# MODULE_PINOUT_WIFI_LAMP_CONTROL.net
KiCad netlist of a schematic drawn in Altium Designer
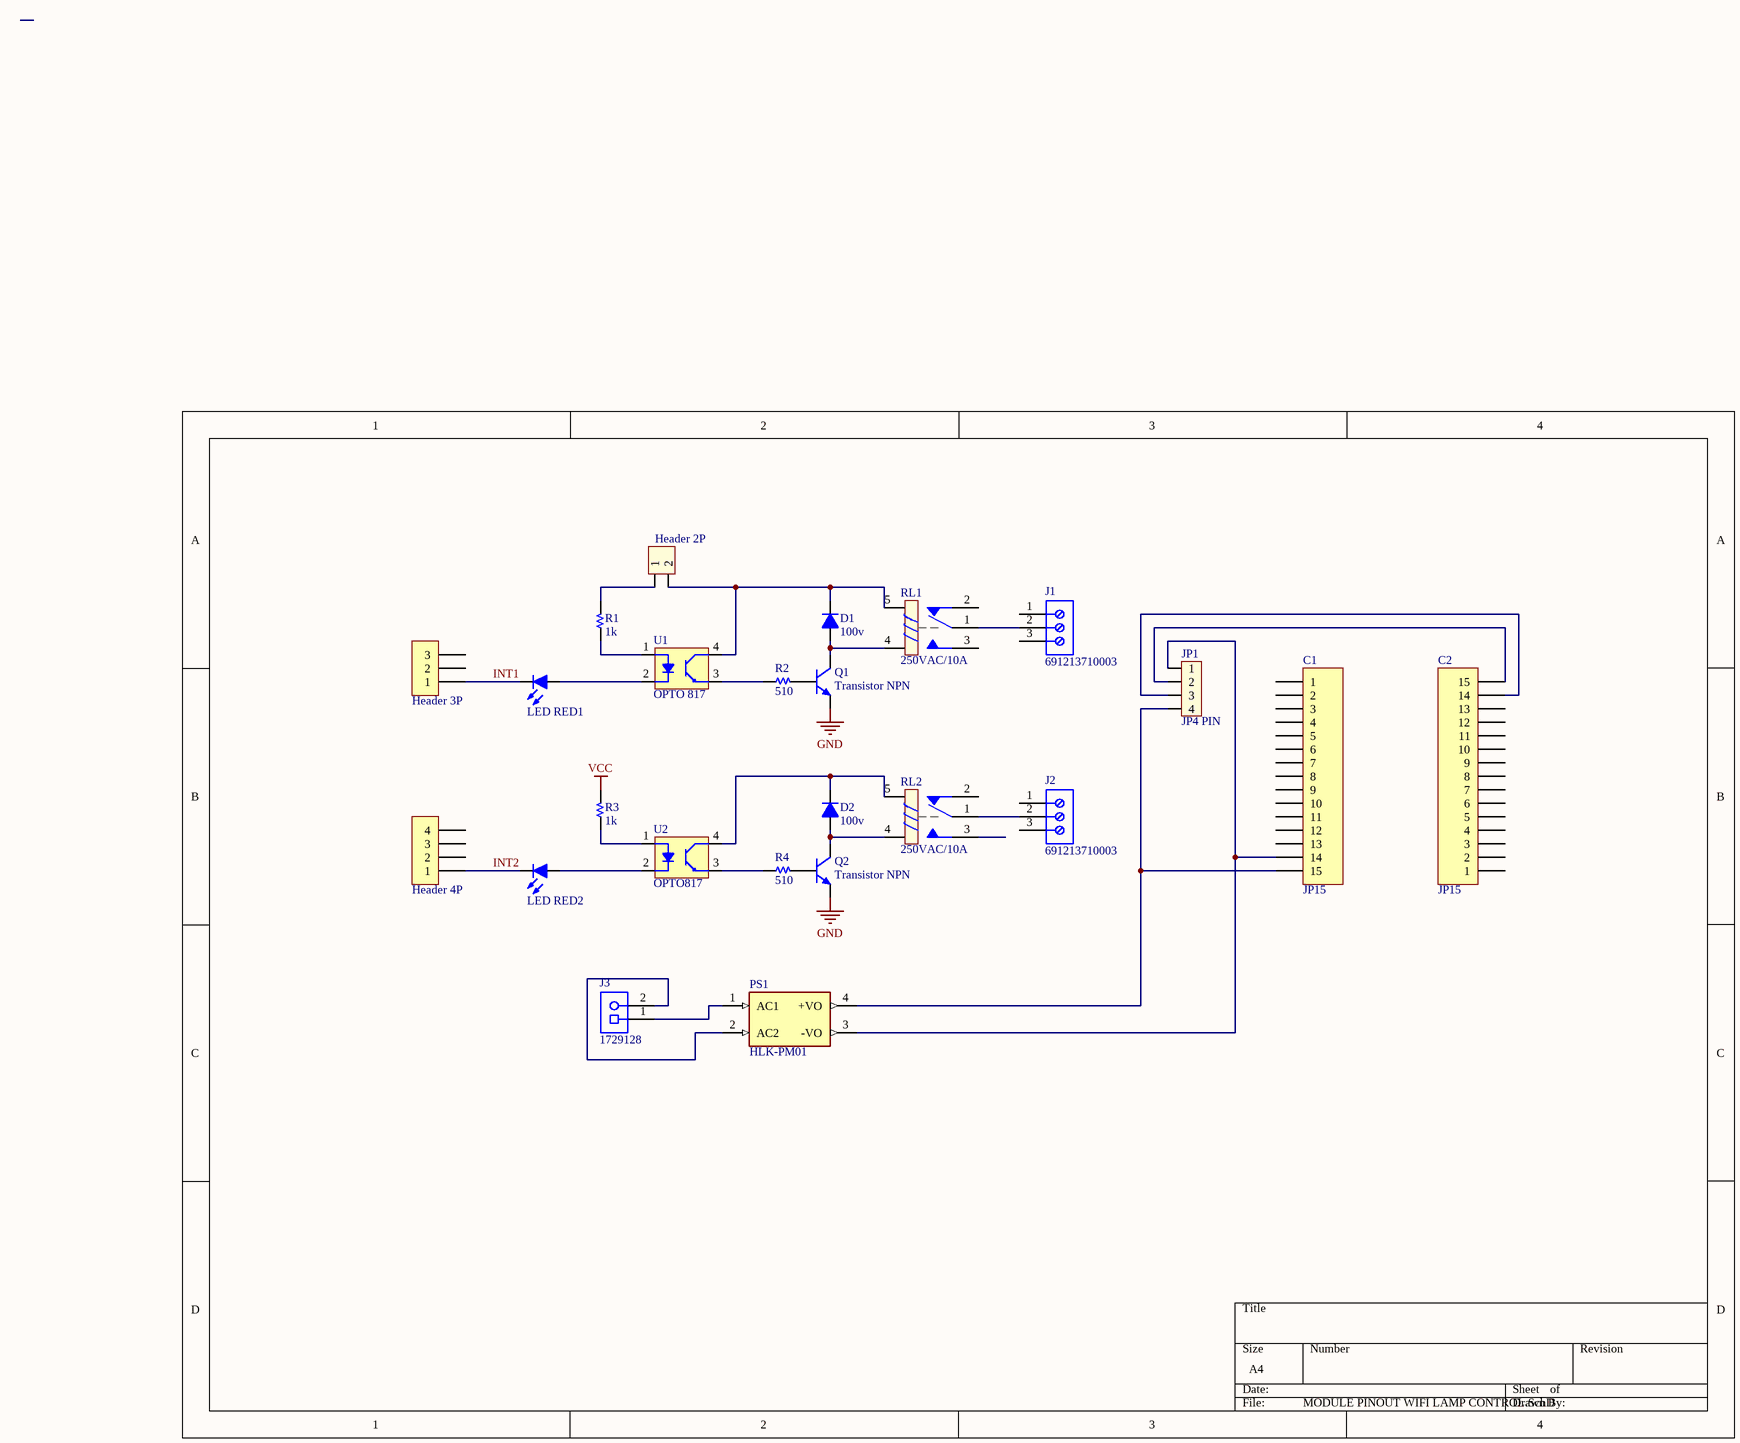
[diagram p0: MODULE PINOUT WIFI LAMP CONTROL.SchDoc]

(export (version "E")
  (design (tool "Eeschema 10.0.6"))
  (components
    (comp (ref "C1")
      (value "JP15")
      (footprint "JP15-C1T")
      (description "WR-PHD 2.54 mm Angled Socket Header")
      (fields
        (field (name "MANUFACTURER") "Würth Elektronik eiSos GmbH")
        (field (name "PARTNO") "613015143121")
        (field (name "CREATED BY") "Karrer Zheng")
      )
      (libsource (lib "") (part "JP15_1"))
    )
    (comp (ref "C2")
      (value "JP15")
      (footprint "JP15-C1T")
      (description "WR-PHD 2.54 mm Angled Socket Header")
      (fields
        (field (name "MANUFACTURER") "Würth Elektronik eiSos GmbH")
        (field (name "PARTNO") "613015143121")
        (field (name "CREATED BY") "Karrer Zheng")
      )
      (libsource (lib "LIBRARY") (part "JP15"))
    )
    (comp (ref "D1")
      (value "100v")
      (footprint "DIODE 0.5A")
      (description "Cắm")
      (libsource (lib "Altium_Lib_by_KhueNguyenCreator") (part "Diode 1N4148"))
    )
    (comp (ref "D2")
      (value "100v")
      (footprint "DIODE 0.5A")
      (description "Cắm")
      (libsource (lib "Altium_Lib_by_KhueNguyenCreator") (part "Diode 1N4148"))
    )
    (comp (ref "H1")
      (value "Header 2P")
      (footprint "XH2.54M-2")
      (description "Cắm")
      (libsource (lib "Altium_Lib_by_KhueNguyenCreator") (part "Header 2P 2.54 Duc Thang"))
    )
    (comp (ref "H2")
      (value "Header 3P")
      (footprint "XH2.54M-3")
      (description "Cắm")
      (libsource (lib "Altium_Lib_by_KhueNguyenCreator") (part "Header 3P 2.54 Duc Thang"))
    )
    (comp (ref "H3")
      (value "Header 4P")
      (footprint "XH2.54M-4")
      (description "Cắm")
      (libsource (lib "Altium_Lib_by_KhueNguyenCreator") (part "Header 4P 2.54 Duc Thang"))
    )
    (comp (ref "J1")
      (value "691213710003")
      (footprint "691213710003")
      (fields (field (name "VOLTAGE") "300V"))
      (libsource (lib "Terminal Block") (part "CMP-1502-02527-2"))
    )
    (comp (ref "J2")
      (value "691213710003")
      (footprint "691213710003")
      (fields (field (name "VOLTAGE") "300V"))
      (libsource (lib "Terminal Block") (part "CMP-1502-02527-2"))
    )
    (comp (ref "J3")
      (value "1729128")
      (footprint "PHOE-1729128-2_V")
      (description "PCB Terminal Block, 13.5 A, 400 V, 2-Pin THD, RoHS, Bulk")
      (fields (field (name "MANUFACTURER") "Phoenix Contact"))
      (libsource (lib "2P Screw Terminal Block") (part "CMP-2000-05815-1"))
    )
    (comp (ref "JP1") (value "JP4 PIN") (footprint "JP4") (libsource (lib "Cty1") (part "JP4")))
    (comp (ref "LED RED1")
      (value "LED RED")
      (footprint "LED 5MM - RED")
      (description "Typical LED")
      (libsource (lib "chipfc_altium_libs") (part "Led"))
    )
    (comp (ref "LED RED2")
      (value "LED RED")
      (footprint "LED 5MM - RED")
      (description "Typical LED")
      (libsource (lib "chipfc_altium_libs") (part "Led"))
    )
    (comp (ref "PS1")
      (value "HLK-PM01")
      (footprint "CONV_HLK-PM01")
      (fields (field (name "MF") "Hi-link") (field (name "MP") "hlk-pm01"))
      (libsource (lib "HLK-PM01") (part "HLK-PM01"))
    )
    (comp (ref "Q1")
      (value "Transistor NPN")
      (footprint "SOT-23")
      (description "NPN Bipolar Transistor")
      (libsource (lib "chipfc_altium_libs") (part "Transistor NPN"))
    )
    (comp (ref "Q2")
      (value "Transistor NPN")
      (footprint "SOT-23")
      (description "NPN Bipolar Transistor")
      (libsource (lib "chipfc_altium_libs") (part "Transistor NPN"))
    )
    (comp (ref "R1")
      (value "1k")
      (footprint "R 1/4W/300")
      (description "Resistor")
      (libsource (lib "chipfc_altium_libs") (part "Resistor"))
    )
    (comp (ref "R2")
      (value "510")
      (footprint "R 1/4W/300")
      (description "Resistor")
      (libsource (lib "chipfc_altium_libs") (part "Resistor"))
    )
    (comp (ref "R3")
      (value "1k")
      (footprint "R 1/4W/300")
      (description "Resistor")
      (libsource (lib "chipfc_altium_libs") (part "Resistor"))
    )
    (comp (ref "R4")
      (value "510")
      (footprint "R 1/4W/300")
      (description "Resistor")
      (libsource (lib "chipfc_altium_libs") (part "Resistor"))
    )
    (comp (ref "RL1")
      (value "250VAC/10A")
      (footprint "Relay 5 Chan SRD")
      (description "Relay 5 Chan")
      (libsource (lib "Altium_Lib_by_KhueNguyenCreator") (part "Relay 5 Chan SRD"))
    )
    (comp (ref "RL2")
      (value "250VAC/10A")
      (footprint "Relay 5 Chan SRD")
      (description "Relay 5 Chan")
      (libsource (lib "Altium_Lib_by_KhueNguyenCreator") (part "Relay 5 Chan SRD"))
    )
    (comp (ref "U1")
      (value "OPTO 817")
      (footprint "DIP4 - PC817")
      (description "Opto PC817B")
      (libsource (lib "chipfc_altium_libs") (part "PC817"))
    )
    (comp (ref "U2")
      (value "OPTO817")
      (footprint "DIP4 - PC817")
      (description "Opto PC817B")
      (libsource (lib "chipfc_altium_libs") (part "PC817"))
    )
  )
  (nets
    (net (code "1") (name "/INT1") (class "Default")
      (node (ref "H2") (pin "1") (pinfunction "1_1") (pintype "passive"))
      (node (ref "LED RED1") (pin "2") (pinfunction "K_2") (pintype "passive"))
    )
    (net (code "2") (name "/INT2") (class "Default")
      (node (ref "H3") (pin "1") (pinfunction "1_1") (pintype "passive"))
      (node (ref "LED RED2") (pin "2") (pinfunction "K_2") (pintype "passive"))
    )
    (net (code "3") (name "GND") (class "Default")
      (node (ref "Q1") (pin "2") (pinfunction "E_2") (pintype "passive"))
      (node (ref "Q2") (pin "2") (pinfunction "E_2") (pintype "passive"))
    )
    (net (code "4") (name "Net-(C2-Pad14)") (class "Default")
      (node (ref "C2") (pin "14") (pinfunction "14_14") (pintype "passive"))
      (node (ref "JP1") (pin "3") (pinfunction "3_3") (pintype "passive"))
    )
    (net (code "5") (name "Net-(C2-Pad15)") (class "Default")
      (node (ref "C2") (pin "15") (pinfunction "15_15") (pintype "passive"))
      (node (ref "JP1") (pin "2") (pinfunction "2_2") (pintype "passive"))
    )
    (net (code "6") (name "Net-(D1-A)") (class "Default")
      (node (ref "D1") (pin "1") (pinfunction "A_1") (pintype "passive"))
      (node (ref "Q1") (pin "3") (pinfunction "C_3") (pintype "passive"))
      (node (ref "RL1") (pin "4") (pinfunction "4_4") (pintype "passive"))
    )
    (net (code "7") (name "Net-(D1-K)") (class "Default")
      (node (ref "D1") (pin "2") (pinfunction "K_2") (pintype "passive"))
      (node (ref "H1") (pin "2") (pinfunction "2_2") (pintype "passive"))
      (node (ref "RL1") (pin "5") (pinfunction "5_5") (pintype "passive"))
      (node (ref "U1") (pin "4") (pinfunction "C_4") (pintype "passive"))
    )
    (net (code "8") (name "Net-(D2-A)") (class "Default")
      (node (ref "D2") (pin "1") (pinfunction "A_1") (pintype "passive"))
      (node (ref "Q2") (pin "3") (pinfunction "C_3") (pintype "passive"))
      (node (ref "RL2") (pin "4") (pinfunction "4_4") (pintype "passive"))
    )
    (net (code "9") (name "Net-(D2-K)") (class "Default")
      (node (ref "D2") (pin "2") (pinfunction "K_2") (pintype "passive"))
      (node (ref "RL2") (pin "5") (pinfunction "5_5") (pintype "passive"))
      (node (ref "U2") (pin "4") (pinfunction "C_4") (pintype "passive"))
    )
    (net (code "10") (name "Net-(H1-Pad1)") (class "Default")
      (node (ref "H1") (pin "1") (pinfunction "1_1") (pintype "passive"))
      (node (ref "R1") (pin "2") (pinfunction "2_2") (pintype "passive"))
    )
    (net (code "11") (name "Net-(J1-Pad2)") (class "Default")
      (node (ref "J1") (pin "2") (pinfunction "2_2") (pintype "passive"))
      (node (ref "RL1") (pin "1") (pinfunction "1_1") (pintype "passive"))
    )
    (net (code "12") (name "Net-(J2-Pad2)") (class "Default")
      (node (ref "J2") (pin "2") (pinfunction "2_2") (pintype "passive"))
      (node (ref "RL2") (pin "1") (pinfunction "1_1") (pintype "passive"))
    )
    (net (code "13") (name "Net-(LED RED1-A)") (class "Default")
      (node (ref "LED RED1") (pin "1") (pinfunction "A_1") (pintype "passive"))
      (node (ref "U1") (pin "2") (pinfunction "K_2") (pintype "passive"))
    )
    (net (code "14") (name "Net-(LED RED2-A)") (class "Default")
      (node (ref "LED RED2") (pin "1") (pinfunction "A_1") (pintype "passive"))
      (node (ref "U2") (pin "2") (pinfunction "K_2") (pintype "passive"))
    )
    (net (code "15") (name "Net-(PS1-+VO)") (class "Default")
      (node (ref "C1") (pin "15") (pinfunction "15_15") (pintype "passive"))
      (node (ref "JP1") (pin "4") (pinfunction "4_4") (pintype "passive"))
      (node (ref "PS1") (pin "4") (pinfunction "+VO_4") (pintype "output"))
    )
    (net (code "16") (name "Net-(PS1--VO)") (class "Default")
      (node (ref "C1") (pin "14") (pinfunction "14_14") (pintype "passive"))
      (node (ref "JP1") (pin "1") (pinfunction "1_1") (pintype "passive"))
      (node (ref "PS1") (pin "3") (pinfunction "-VO_3") (pintype "output"))
    )
    (net (code "17") (name "Net-(PS1-AC1)") (class "Default")
      (node (ref "J3") (pin "1") (pinfunction "1_1") (pintype "passive"))
      (node (ref "PS1") (pin "1") (pinfunction "AC1_1") (pintype "input"))
    )
    (net (code "18") (name "Net-(PS1-AC2)") (class "Default")
      (node (ref "J3") (pin "2") (pinfunction "2_2") (pintype "passive"))
      (node (ref "PS1") (pin "2") (pinfunction "AC2_2") (pintype "input"))
    )
    (net (code "19") (name "Net-(Q1-B)") (class "Default")
      (node (ref "Q1") (pin "1") (pinfunction "B_1") (pintype "passive"))
      (node (ref "R2") (pin "2") (pinfunction "2_2") (pintype "passive"))
    )
    (net (code "20") (name "Net-(Q2-B)") (class "Default")
      (node (ref "Q2") (pin "1") (pinfunction "B_1") (pintype "passive"))
      (node (ref "R4") (pin "2") (pinfunction "2_2") (pintype "passive"))
    )
    (net (code "21") (name "Net-(U1-A)") (class "Default")
      (node (ref "R1") (pin "1") (pinfunction "1_1") (pintype "passive"))
      (node (ref "U1") (pin "1") (pinfunction "A_1") (pintype "passive"))
    )
    (net (code "22") (name "Net-(U1-E)") (class "Default")
      (node (ref "R2") (pin "1") (pinfunction "1_1") (pintype "passive"))
      (node (ref "U1") (pin "3") (pinfunction "E_3") (pintype "passive"))
    )
    (net (code "23") (name "Net-(U2-A)") (class "Default")
      (node (ref "R3") (pin "1") (pinfunction "1_1") (pintype "passive"))
      (node (ref "U2") (pin "1") (pinfunction "A_1") (pintype "passive"))
    )
    (net (code "24") (name "Net-(U2-E)") (class "Default")
      (node (ref "R4") (pin "1") (pinfunction "1_1") (pintype "passive"))
      (node (ref "U2") (pin "3") (pinfunction "E_3") (pintype "passive"))
    )
    (net (code "25") (name "VCC") (class "Default")
      (node (ref "R3") (pin "2") (pinfunction "2_2") (pintype "passive"))
    )
    (net (code "26") (name "unconnected-(C1-Pad1)") (class "Default")
      (node (ref "C1") (pin "1") (pinfunction "1_1") (pintype "passive"))
    )
    (net (code "27") (name "unconnected-(C1-Pad2)") (class "Default")
      (node (ref "C1") (pin "2") (pinfunction "2_2") (pintype "passive"))
    )
    (net (code "28") (name "unconnected-(C1-Pad3)") (class "Default")
      (node (ref "C1") (pin "3") (pinfunction "3_3") (pintype "passive"))
    )
    (net (code "29") (name "unconnected-(C1-Pad4)") (class "Default")
      (node (ref "C1") (pin "4") (pinfunction "4_4") (pintype "passive"))
    )
    (net (code "30") (name "unconnected-(C1-Pad5)") (class "Default")
      (node (ref "C1") (pin "5") (pinfunction "5_5") (pintype "passive"))
    )
    (net (code "31") (name "unconnected-(C1-Pad6)") (class "Default")
      (node (ref "C1") (pin "6") (pinfunction "6_6") (pintype "passive"))
    )
    (net (code "32") (name "unconnected-(C1-Pad7)") (class "Default")
      (node (ref "C1") (pin "7") (pinfunction "7_7") (pintype "passive"))
    )
    (net (code "33") (name "unconnected-(C1-Pad8)") (class "Default")
      (node (ref "C1") (pin "8") (pinfunction "8_8") (pintype "passive"))
    )
    (net (code "34") (name "unconnected-(C1-Pad9)") (class "Default")
      (node (ref "C1") (pin "9") (pinfunction "9_9") (pintype "passive"))
    )
    (net (code "35") (name "unconnected-(C1-Pad10)") (class "Default")
      (node (ref "C1") (pin "10") (pinfunction "10_10") (pintype "passive"))
    )
    (net (code "36") (name "unconnected-(C1-Pad11)") (class "Default")
      (node (ref "C1") (pin "11") (pinfunction "11_11") (pintype "passive"))
    )
    (net (code "37") (name "unconnected-(C1-Pad12)") (class "Default")
      (node (ref "C1") (pin "12") (pinfunction "12_12") (pintype "passive"))
    )
    (net (code "38") (name "unconnected-(C1-Pad13)") (class "Default")
      (node (ref "C1") (pin "13") (pinfunction "13_13") (pintype "passive"))
    )
    (net (code "39") (name "unconnected-(C2-Pad1)") (class "Default")
      (node (ref "C2") (pin "1") (pinfunction "1_1") (pintype "passive"))
    )
    (net (code "40") (name "unconnected-(C2-Pad2)") (class "Default")
      (node (ref "C2") (pin "2") (pinfunction "2_2") (pintype "passive"))
    )
    (net (code "41") (name "unconnected-(C2-Pad3)") (class "Default")
      (node (ref "C2") (pin "3") (pinfunction "3_3") (pintype "passive"))
    )
    (net (code "42") (name "unconnected-(C2-Pad4)") (class "Default")
      (node (ref "C2") (pin "4") (pinfunction "4_4") (pintype "passive"))
    )
    (net (code "43") (name "unconnected-(C2-Pad5)") (class "Default")
      (node (ref "C2") (pin "5") (pinfunction "5_5") (pintype "passive"))
    )
    (net (code "44") (name "unconnected-(C2-Pad6)") (class "Default")
      (node (ref "C2") (pin "6") (pinfunction "6_6") (pintype "passive"))
    )
    (net (code "45") (name "unconnected-(C2-Pad7)") (class "Default")
      (node (ref "C2") (pin "7") (pinfunction "7_7") (pintype "passive"))
    )
    (net (code "46") (name "unconnected-(C2-Pad8)") (class "Default")
      (node (ref "C2") (pin "8") (pinfunction "8_8") (pintype "passive"))
    )
    (net (code "47") (name "unconnected-(C2-Pad9)") (class "Default")
      (node (ref "C2") (pin "9") (pinfunction "9_9") (pintype "passive"))
    )
    (net (code "48") (name "unconnected-(C2-Pad10)") (class "Default")
      (node (ref "C2") (pin "10") (pinfunction "10_10") (pintype "passive"))
    )
    (net (code "49") (name "unconnected-(C2-Pad11)") (class "Default")
      (node (ref "C2") (pin "11") (pinfunction "11_11") (pintype "passive"))
    )
    (net (code "50") (name "unconnected-(C2-Pad12)") (class "Default")
      (node (ref "C2") (pin "12") (pinfunction "12_12") (pintype "passive"))
    )
    (net (code "51") (name "unconnected-(C2-Pad13)") (class "Default")
      (node (ref "C2") (pin "13") (pinfunction "13_13") (pintype "passive"))
    )
    (net (code "52") (name "unconnected-(H2-Pad2)") (class "Default")
      (node (ref "H2") (pin "2") (pinfunction "2_2") (pintype "passive"))
    )
    (net (code "53") (name "unconnected-(H2-Pad3)") (class "Default")
      (node (ref "H2") (pin "3") (pinfunction "3_3") (pintype "passive"))
    )
    (net (code "54") (name "unconnected-(H3-Pad2)") (class "Default")
      (node (ref "H3") (pin "2") (pinfunction "2_2") (pintype "passive"))
    )
    (net (code "55") (name "unconnected-(H3-Pad3)") (class "Default")
      (node (ref "H3") (pin "3") (pinfunction "3_3") (pintype "passive"))
    )
    (net (code "56") (name "unconnected-(H3-Pad4)") (class "Default")
      (node (ref "H3") (pin "4") (pinfunction "4_4") (pintype "passive"))
    )
    (net (code "57") (name "unconnected-(J1-Pad1)") (class "Default")
      (node (ref "J1") (pin "1") (pinfunction "1_1") (pintype "passive"))
    )
    (net (code "58") (name "unconnected-(J1-Pad3)") (class "Default")
      (node (ref "J1") (pin "3") (pinfunction "3_3") (pintype "passive"))
    )
    (net (code "59") (name "unconnected-(J2-Pad1)") (class "Default")
      (node (ref "J2") (pin "1") (pinfunction "1_1") (pintype "passive"))
    )
    (net (code "60") (name "unconnected-(J2-Pad3)") (class "Default")
      (node (ref "J2") (pin "3") (pinfunction "3_3") (pintype "passive"))
    )
    (net (code "61") (name "unconnected-(RL1-Pad2)") (class "Default")
      (node (ref "RL1") (pin "2") (pinfunction "2_2") (pintype "passive"))
    )
    (net (code "62") (name "unconnected-(RL1-Pad3)") (class "Default")
      (node (ref "RL1") (pin "3") (pinfunction "3_3") (pintype "passive"))
    )
    (net (code "63") (name "unconnected-(RL2-Pad2)") (class "Default")
      (node (ref "RL2") (pin "2") (pinfunction "2_2") (pintype "passive"))
    )
    (net (code "64") (name "unconnected-(RL2-Pad3)") (class "Default")
      (node (ref "RL2") (pin "3") (pinfunction "3_3") (pintype "passive"))
    )
  )
)
